# design.net
KiCad netlist of a schematic drawn in Altium Designer
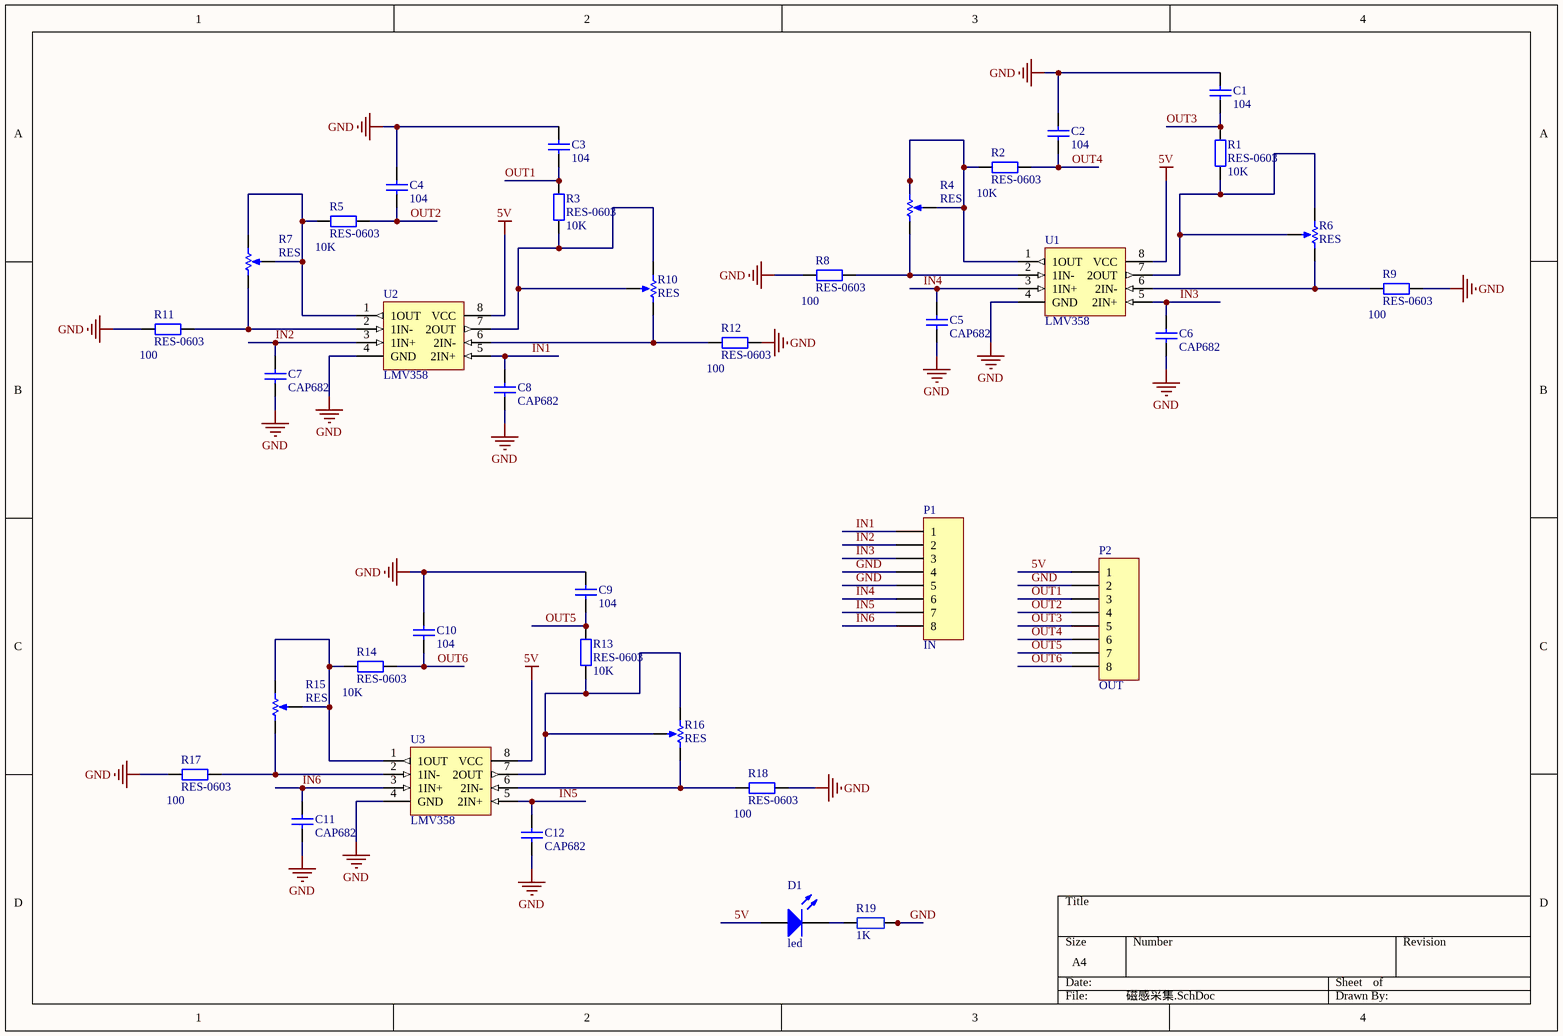
[diagram p0: 磁感采集.SchDoc]

(export (version "E")
  (design (tool "Eeschema 10.0.6"))
  (components
    (comp (ref "C1") (value "104") (footprint "CAP-0603") (libsource (lib "wmh_commom") (part "CAP-0603")))
    (comp (ref "C2") (value "104") (footprint "CAP-0603") (libsource (lib "wmh_commom") (part "CAP-0603")))
    (comp (ref "C3") (value "104") (footprint "CAP-0603") (libsource (lib "wmh_commom") (part "CAP-0603")))
    (comp (ref "C4") (value "104") (footprint "CAP-0603") (libsource (lib "wmh_commom") (part "CAP-0603")))
    (comp (ref "C5") (value "CAP682") (footprint "CAP682") (libsource (lib "wmh_commom") (part "CAP 682")))
    (comp (ref "C6") (value "CAP682") (footprint "CAP682") (libsource (lib "wmh_commom") (part "CAP 682")))
    (comp (ref "C7") (value "CAP682") (footprint "CAP682") (libsource (lib "wmh_commom") (part "CAP 682")))
    (comp (ref "C8") (value "CAP682") (footprint "CAP682") (libsource (lib "wmh_commom") (part "CAP 682")))
    (comp (ref "C9") (value "104") (footprint "CAP-0603") (libsource (lib "wmh_commom") (part "CAP-0603")))
    (comp (ref "C10") (value "104") (footprint "CAP-0603") (libsource (lib "wmh_commom") (part "CAP-0603")))
    (comp (ref "C11") (value "CAP682") (footprint "CAP682") (libsource (lib "wmh_commom") (part "CAP 682")))
    (comp (ref "C12") (value "CAP682") (footprint "CAP682") (libsource (lib "wmh_commom") (part "CAP 682")))
    (comp (ref "D1") (value "led") (footprint "led0805") (libsource (lib "Driver") (part "led0805")))
    (comp (ref "P1")
      (value "IN")
      (footprint "HDR1X8")
      (description "Header, 8-Pin")
      (fields (field (name "PUBLISHER") "Altium Limited"))
      (libsource (lib "Common Headers") (part "Header 8"))
    )
    (comp (ref "P2")
      (value "OUT")
      (footprint "HDR1X8")
      (description "Header, 8-Pin")
      (fields (field (name "PUBLISHER") "Altium Limited"))
      (libsource (lib "Common Headers") (part "Header 8"))
    )
    (comp (ref "R1")
      (value "RES-0603")
      (footprint "RES-0603")
      (fields (field (name "ALTIUM_UNNAMED_1") "10K"))
      (libsource (lib "wmh_commom") (part "RES-0603"))
    )
    (comp (ref "R2")
      (value "RES-0603")
      (footprint "RES-0603")
      (fields (field (name "ALTIUM_UNNAMED_1") "10K"))
      (libsource (lib "wmh_commom") (part "RES-0603"))
    )
    (comp (ref "R3")
      (value "RES-0603")
      (footprint "RES-0603")
      (fields (field (name "ALTIUM_UNNAMED_1") "10K"))
      (libsource (lib "wmh_commom") (part "RES-0603"))
    )
    (comp (ref "R4")
      (value "RES")
      (footprint "RES-change-3362P")
      (libsource (lib "wmh_commom") (part "RES-change-3362P"))
    )
    (comp (ref "R5")
      (value "RES-0603")
      (footprint "RES-0603")
      (fields (field (name "ALTIUM_UNNAMED_1") "10K"))
      (libsource (lib "wmh_commom") (part "RES-0603"))
    )
    (comp (ref "R6")
      (value "RES")
      (footprint "RES-change-3362P")
      (libsource (lib "wmh_commom") (part "RES-change-3362P"))
    )
    (comp (ref "R7")
      (value "RES")
      (footprint "RES-change-3362P")
      (libsource (lib "wmh_commom") (part "RES-change-3362P"))
    )
    (comp (ref "R8")
      (value "RES-0603")
      (footprint "RES-0603")
      (fields (field (name "ALTIUM_UNNAMED_1") "100"))
      (libsource (lib "wmh_commom") (part "RES-0603"))
    )
    (comp (ref "R9")
      (value "RES-0603")
      (footprint "RES-0603")
      (fields (field (name "ALTIUM_UNNAMED_1") "100"))
      (libsource (lib "wmh_commom") (part "RES-0603"))
    )
    (comp (ref "R10")
      (value "RES")
      (footprint "RES-change-3362P")
      (libsource (lib "wmh_commom") (part "RES-change-3362P"))
    )
    (comp (ref "R11")
      (value "RES-0603")
      (footprint "RES-0603")
      (fields (field (name "ALTIUM_UNNAMED_1") "100"))
      (libsource (lib "wmh_commom") (part "RES-0603"))
    )
    (comp (ref "R12")
      (value "RES-0603")
      (footprint "RES-0603")
      (fields (field (name "ALTIUM_UNNAMED_1") "100"))
      (libsource (lib "wmh_commom") (part "RES-0603"))
    )
    (comp (ref "R13")
      (value "RES-0603")
      (footprint "RES-0603")
      (fields (field (name "ALTIUM_UNNAMED_1") "10K"))
      (libsource (lib "wmh_commom") (part "RES-0603"))
    )
    (comp (ref "R14")
      (value "RES-0603")
      (footprint "RES-0603")
      (fields (field (name "ALTIUM_UNNAMED_1") "10K"))
      (libsource (lib "wmh_commom") (part "RES-0603"))
    )
    (comp (ref "R15")
      (value "RES")
      (footprint "RES-change-3362P")
      (libsource (lib "wmh_commom") (part "RES-change-3362P"))
    )
    (comp (ref "R16")
      (value "RES")
      (footprint "RES-change-3362P")
      (libsource (lib "wmh_commom") (part "RES-change-3362P"))
    )
    (comp (ref "R17")
      (value "RES-0603")
      (footprint "RES-0603")
      (fields (field (name "ALTIUM_UNNAMED_1") "100"))
      (libsource (lib "wmh_commom") (part "RES-0603"))
    )
    (comp (ref "R18")
      (value "RES-0603")
      (footprint "RES-0603")
      (fields (field (name "ALTIUM_UNNAMED_1") "100"))
      (libsource (lib "wmh_commom") (part "RES-0603"))
    )
    (comp (ref "R19")
      (value "RES-0805")
      (footprint "RES-0805")
      (fields (field (name "ALTIUM_UNNAMED_1") "1K"))
      (libsource (lib "ZZY_common") (part "RES-0805"))
    )
    (comp (ref "U1") (value "LMV358") (footprint "SOP-8") (libsource (lib "KING_IC") (part "LMV358")))
    (comp (ref "U2") (value "LMV358") (footprint "SOP-8") (libsource (lib "KING_IC") (part "LMV358")))
    (comp (ref "U3") (value "LMV358") (footprint "SOP-8") (libsource (lib "KING_IC") (part "LMV358")))
  )
  (nets
    (net (code "1") (name "/IN1") (class "Default")
      (node (ref "C8") (pin "1") (pinfunction "1_1") (pintype "passive"))
      (node (ref "P1") (pin "1") (pinfunction "1_1") (pintype "passive"))
      (node (ref "U2") (pin "5") (pinfunction "2IN+_5") (pintype "input"))
    )
    (net (code "2") (name "/IN2") (class "Default")
      (node (ref "C7") (pin "2") (pinfunction "2_2") (pintype "passive"))
      (node (ref "P1") (pin "2") (pinfunction "2_2") (pintype "passive"))
      (node (ref "U2") (pin "3") (pinfunction "1IN+_3") (pintype "input"))
    )
    (net (code "3") (name "/IN3") (class "Default")
      (node (ref "C6") (pin "1") (pinfunction "1_1") (pintype "passive"))
      (node (ref "P1") (pin "3") (pinfunction "3_3") (pintype "passive"))
      (node (ref "U1") (pin "5") (pinfunction "2IN+_5") (pintype "input"))
    )
    (net (code "4") (name "/IN4") (class "Default")
      (node (ref "C5") (pin "2") (pinfunction "2_2") (pintype "passive"))
      (node (ref "P1") (pin "6") (pinfunction "6_6") (pintype "passive"))
      (node (ref "U1") (pin "3") (pinfunction "1IN+_3") (pintype "input"))
    )
    (net (code "5") (name "/IN5") (class "Default")
      (node (ref "C12") (pin "1") (pinfunction "1_1") (pintype "passive"))
      (node (ref "P1") (pin "7") (pinfunction "7_7") (pintype "passive"))
      (node (ref "U3") (pin "5") (pinfunction "2IN+_5") (pintype "input"))
    )
    (net (code "6") (name "/IN6") (class "Default")
      (node (ref "C11") (pin "2") (pinfunction "2_2") (pintype "passive"))
      (node (ref "P1") (pin "8") (pinfunction "8_8") (pintype "passive"))
      (node (ref "U3") (pin "3") (pinfunction "1IN+_3") (pintype "input"))
    )
    (net (code "7") (name "/OUT1") (class "Default")
      (node (ref "C3") (pin "1") (pinfunction "1_1") (pintype "passive"))
      (node (ref "P2") (pin "3") (pinfunction "3_3") (pintype "passive"))
      (node (ref "R3") (pin "2") (pinfunction "2_2") (pintype "passive"))
    )
    (net (code "8") (name "/OUT2") (class "Default")
      (node (ref "C4") (pin "1") (pinfunction "1_1") (pintype "passive"))
      (node (ref "P2") (pin "4") (pinfunction "4_4") (pintype "passive"))
      (node (ref "R5") (pin "2") (pinfunction "2_2") (pintype "passive"))
    )
    (net (code "9") (name "/OUT3") (class "Default")
      (node (ref "C1") (pin "1") (pinfunction "1_1") (pintype "passive"))
      (node (ref "P2") (pin "5") (pinfunction "5_5") (pintype "passive"))
      (node (ref "R1") (pin "2") (pinfunction "2_2") (pintype "passive"))
    )
    (net (code "10") (name "/OUT4") (class "Default")
      (node (ref "C2") (pin "1") (pinfunction "1_1") (pintype "passive"))
      (node (ref "P2") (pin "6") (pinfunction "6_6") (pintype "passive"))
      (node (ref "R2") (pin "2") (pinfunction "2_2") (pintype "passive"))
    )
    (net (code "11") (name "/OUT5") (class "Default")
      (node (ref "C9") (pin "1") (pinfunction "1_1") (pintype "passive"))
      (node (ref "P2") (pin "7") (pinfunction "7_7") (pintype "passive"))
      (node (ref "R13") (pin "2") (pinfunction "2_2") (pintype "passive"))
    )
    (net (code "12") (name "/OUT6") (class "Default")
      (node (ref "C10") (pin "1") (pinfunction "1_1") (pintype "passive"))
      (node (ref "P2") (pin "8") (pinfunction "8_8") (pintype "passive"))
      (node (ref "R14") (pin "2") (pinfunction "2_2") (pintype "passive"))
    )
    (net (code "13") (name "5V") (class "Default")
      (node (ref "D1") (pin "1") (pinfunction "A_1") (pintype "passive"))
      (node (ref "P2") (pin "1") (pinfunction "1_1") (pintype "passive"))
      (node (ref "U1") (pin "8") (pinfunction "VCC_8") (pintype "power_in"))
      (node (ref "U2") (pin "8") (pinfunction "VCC_8") (pintype "power_in"))
      (node (ref "U3") (pin "8") (pinfunction "VCC_8") (pintype "power_in"))
    )
    (net (code "14") (name "GND") (class "Default")
      (node (ref "C1") (pin "2") (pinfunction "2_2") (pintype "passive"))
      (node (ref "C10") (pin "2") (pinfunction "2_2") (pintype "passive"))
      (node (ref "C11") (pin "1") (pinfunction "1_1") (pintype "passive"))
      (node (ref "C12") (pin "2") (pinfunction "2_2") (pintype "passive"))
      (node (ref "C2") (pin "2") (pinfunction "2_2") (pintype "passive"))
      (node (ref "C3") (pin "2") (pinfunction "2_2") (pintype "passive"))
      (node (ref "C4") (pin "2") (pinfunction "2_2") (pintype "passive"))
      (node (ref "C5") (pin "1") (pinfunction "1_1") (pintype "passive"))
      (node (ref "C6") (pin "2") (pinfunction "2_2") (pintype "passive"))
      (node (ref "C7") (pin "1") (pinfunction "1_1") (pintype "passive"))
      (node (ref "C8") (pin "2") (pinfunction "2_2") (pintype "passive"))
      (node (ref "C9") (pin "2") (pinfunction "2_2") (pintype "passive"))
      (node (ref "P1") (pin "4") (pinfunction "4_4") (pintype "passive"))
      (node (ref "P1") (pin "5") (pinfunction "5_5") (pintype "passive"))
      (node (ref "P2") (pin "2") (pinfunction "2_2") (pintype "passive"))
      (node (ref "R11") (pin "1") (pinfunction "1_1") (pintype "passive"))
      (node (ref "R12") (pin "2") (pinfunction "2_2") (pintype "passive"))
      (node (ref "R17") (pin "1") (pinfunction "1_1") (pintype "passive"))
      (node (ref "R18") (pin "2") (pinfunction "2_2") (pintype "passive"))
      (node (ref "R19") (pin "2") (pinfunction "2_2") (pintype "passive"))
      (node (ref "R8") (pin "1") (pinfunction "1_1") (pintype "passive"))
      (node (ref "R9") (pin "2") (pinfunction "2_2") (pintype "passive"))
      (node (ref "U1") (pin "4") (pinfunction "GND_4") (pintype "power_in"))
      (node (ref "U2") (pin "4") (pinfunction "GND_4") (pintype "power_in"))
      (node (ref "U3") (pin "4") (pinfunction "GND_4") (pintype "power_in"))
    )
    (net (code "15") (name "Net-(D1-K)") (class "Default")
      (node (ref "D1") (pin "2") (pinfunction "K_2") (pintype "passive"))
      (node (ref "R19") (pin "1") (pinfunction "1_1") (pintype "passive"))
    )
    (net (code "16") (name "Net-(R4-BOT)") (class "Default")
      (node (ref "R2") (pin "1") (pinfunction "1_1") (pintype "passive"))
      (node (ref "R4") (pin "2") (pinfunction "BOT_2") (pintype "passive"))
      (node (ref "R4") (pin "3") (pinfunction "TAP_3") (pintype "passive"))
      (node (ref "U1") (pin "1") (pinfunction "1OUT_1") (pintype "output"))
    )
    (net (code "17") (name "Net-(R4-TOP)") (class "Default")
      (node (ref "R4") (pin "1") (pinfunction "TOP_1") (pintype "passive"))
      (node (ref "R8") (pin "2") (pinfunction "2_2") (pintype "passive"))
      (node (ref "U1") (pin "2") (pinfunction "1IN-_2") (pintype "input"))
    )
    (net (code "18") (name "Net-(R6-BOT)") (class "Default")
      (node (ref "R6") (pin "2") (pinfunction "BOT_2") (pintype "passive"))
      (node (ref "R9") (pin "1") (pinfunction "1_1") (pintype "passive"))
      (node (ref "U1") (pin "6") (pinfunction "2IN-_6") (pintype "input"))
    )
    (net (code "19") (name "Net-(R6-TAP)") (class "Default")
      (node (ref "R1") (pin "1") (pinfunction "1_1") (pintype "passive"))
      (node (ref "R6") (pin "1") (pinfunction "TOP_1") (pintype "passive"))
      (node (ref "R6") (pin "3") (pinfunction "TAP_3") (pintype "passive"))
      (node (ref "U1") (pin "7") (pinfunction "2OUT_7") (pintype "output"))
    )
    (net (code "20") (name "Net-(R7-BOT)") (class "Default")
      (node (ref "R5") (pin "1") (pinfunction "1_1") (pintype "passive"))
      (node (ref "R7") (pin "2") (pinfunction "BOT_2") (pintype "passive"))
      (node (ref "R7") (pin "3") (pinfunction "TAP_3") (pintype "passive"))
      (node (ref "U2") (pin "1") (pinfunction "1OUT_1") (pintype "output"))
    )
    (net (code "21") (name "Net-(R7-TOP)") (class "Default")
      (node (ref "R11") (pin "2") (pinfunction "2_2") (pintype "passive"))
      (node (ref "R7") (pin "1") (pinfunction "TOP_1") (pintype "passive"))
      (node (ref "U2") (pin "2") (pinfunction "1IN-_2") (pintype "input"))
    )
    (net (code "22") (name "Net-(R10-BOT)") (class "Default")
      (node (ref "R10") (pin "2") (pinfunction "BOT_2") (pintype "passive"))
      (node (ref "R12") (pin "1") (pinfunction "1_1") (pintype "passive"))
      (node (ref "U2") (pin "6") (pinfunction "2IN-_6") (pintype "input"))
    )
    (net (code "23") (name "Net-(R10-TAP)") (class "Default")
      (node (ref "R10") (pin "1") (pinfunction "TOP_1") (pintype "passive"))
      (node (ref "R10") (pin "3") (pinfunction "TAP_3") (pintype "passive"))
      (node (ref "R3") (pin "1") (pinfunction "1_1") (pintype "passive"))
      (node (ref "U2") (pin "7") (pinfunction "2OUT_7") (pintype "output"))
    )
    (net (code "24") (name "Net-(R15-BOT)") (class "Default")
      (node (ref "R14") (pin "1") (pinfunction "1_1") (pintype "passive"))
      (node (ref "R15") (pin "2") (pinfunction "BOT_2") (pintype "passive"))
      (node (ref "R15") (pin "3") (pinfunction "TAP_3") (pintype "passive"))
      (node (ref "U3") (pin "1") (pinfunction "1OUT_1") (pintype "output"))
    )
    (net (code "25") (name "Net-(R15-TOP)") (class "Default")
      (node (ref "R15") (pin "1") (pinfunction "TOP_1") (pintype "passive"))
      (node (ref "R17") (pin "2") (pinfunction "2_2") (pintype "passive"))
      (node (ref "U3") (pin "2") (pinfunction "1IN-_2") (pintype "input"))
    )
    (net (code "26") (name "Net-(R16-BOT)") (class "Default")
      (node (ref "R16") (pin "2") (pinfunction "BOT_2") (pintype "passive"))
      (node (ref "R18") (pin "1") (pinfunction "1_1") (pintype "passive"))
      (node (ref "U3") (pin "6") (pinfunction "2IN-_6") (pintype "input"))
    )
    (net (code "27") (name "Net-(R16-TAP)") (class "Default")
      (node (ref "R13") (pin "1") (pinfunction "1_1") (pintype "passive"))
      (node (ref "R16") (pin "1") (pinfunction "TOP_1") (pintype "passive"))
      (node (ref "R16") (pin "3") (pinfunction "TAP_3") (pintype "passive"))
      (node (ref "U3") (pin "7") (pinfunction "2OUT_7") (pintype "output"))
    )
  )
)
